# ProProject_audio_project_2024-04-19.net
KiCad netlist of a schematic drawn in EasyEDA Pro
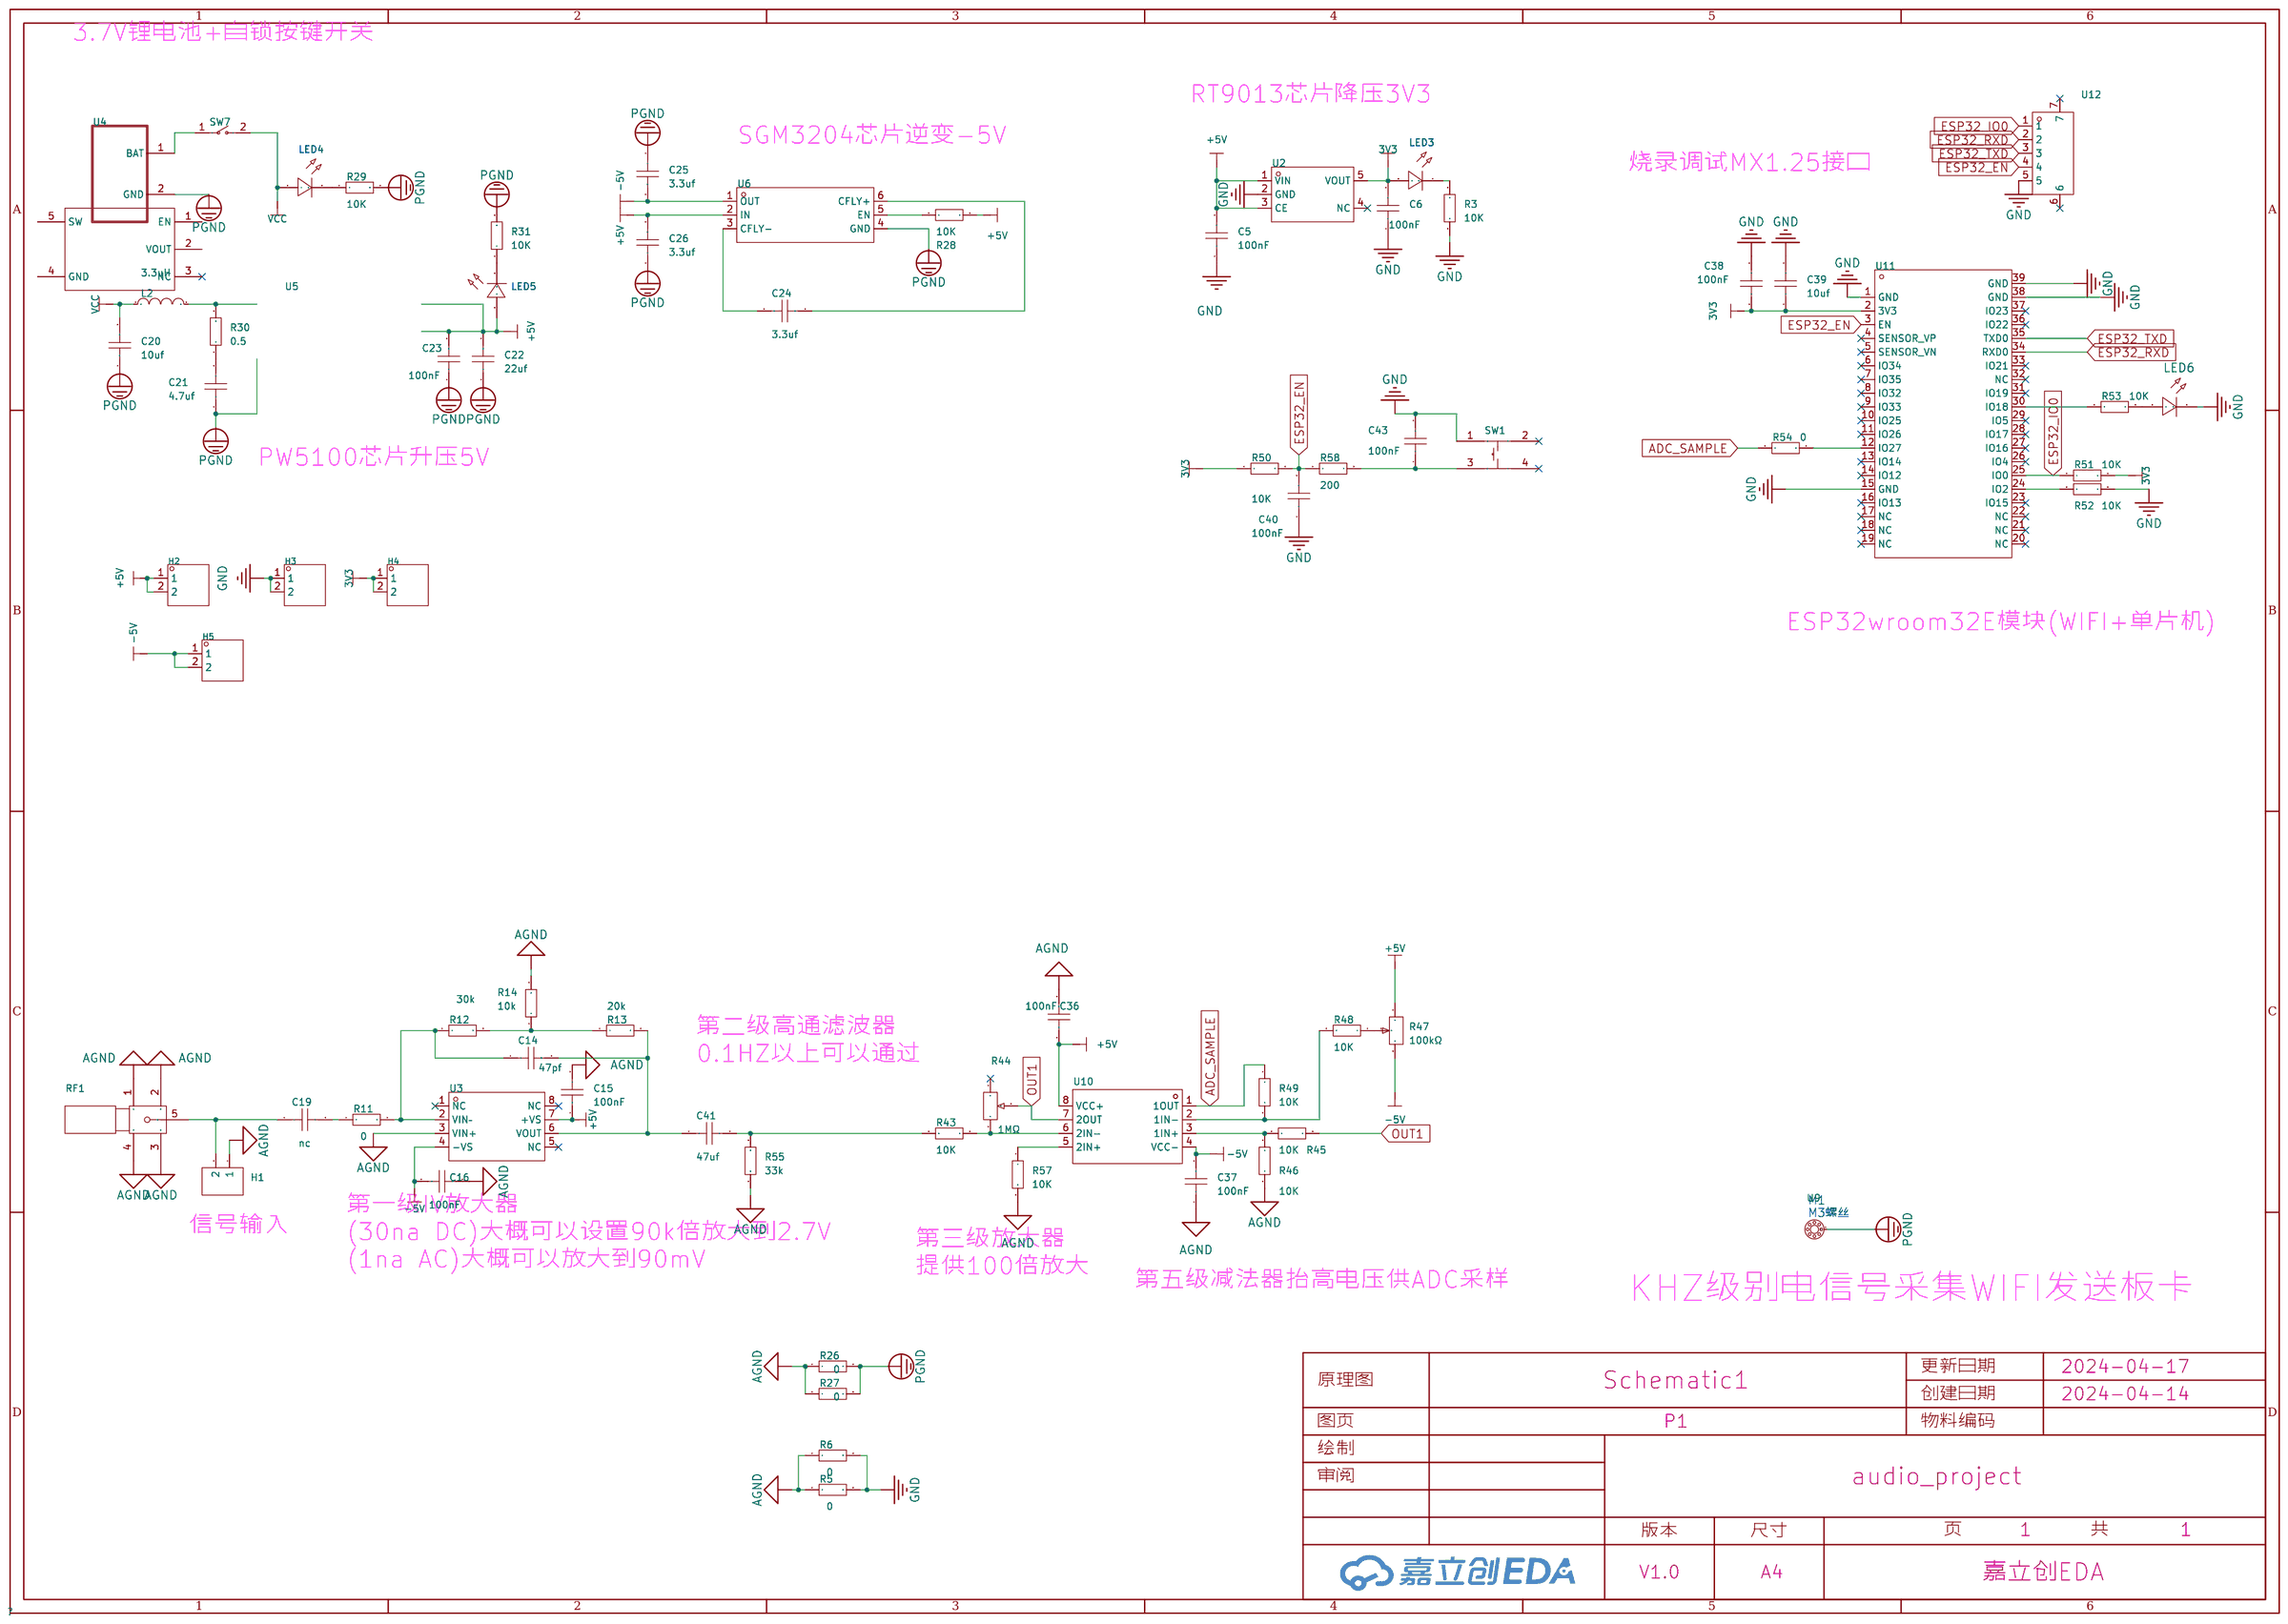
[diagram p0: schematic sheet]

(export (version "E")
  (design (tool "Eeschema 10.0.6"))
  (components
    (comp (ref "C5")
      (value "100nF")
      (footprint "easyedapro:C0805")
      (libsource (lib "easyedapro") (part "CapAcitance"))
    )
    (comp (ref "C6")
      (value "100nF")
      (footprint "easyedapro:C0805")
      (libsource (lib "easyedapro") (part "CapAcitance"))
    )
    (comp (ref "C14")
      (value "47pf")
      (footprint "easyedapro:C0805")
      (libsource (lib "easyedapro") (part "CapAcitance"))
    )
    (comp (ref "C15")
      (value "100nF")
      (footprint "easyedapro:C0805")
      (libsource (lib "easyedapro") (part "CapAcitance"))
    )
    (comp (ref "C16")
      (value "100nF")
      (footprint "easyedapro:C0805")
      (libsource (lib "easyedapro") (part "CapAcitance"))
    )
    (comp (ref "C19")
      (value "nc")
      (footprint "easyedapro:C0805")
      (libsource (lib "easyedapro") (part "CapAcitance"))
    )
    (comp (ref "C20")
      (value "10uf")
      (footprint "easyedapro:C0805")
      (libsource (lib "easyedapro") (part "CapAcitance"))
    )
    (comp (ref "C21")
      (value "4.7uf")
      (footprint "easyedapro:C0805")
      (libsource (lib "easyedapro") (part "CapAcitance"))
    )
    (comp (ref "C22")
      (value "22uf")
      (footprint "easyedapro:C0805")
      (libsource (lib "easyedapro") (part "CapAcitance"))
    )
    (comp (ref "C23")
      (value "100nF")
      (footprint "easyedapro:C0805")
      (libsource (lib "easyedapro") (part "CapAcitance"))
    )
    (comp (ref "C24")
      (value "3.3uf")
      (footprint "easyedapro:C0805")
      (libsource (lib "easyedapro") (part "CapAcitance"))
    )
    (comp (ref "C25")
      (value "3.3uf")
      (footprint "easyedapro:C0805")
      (libsource (lib "easyedapro") (part "CapAcitance"))
    )
    (comp (ref "C26")
      (value "3.3uf")
      (footprint "easyedapro:C0805")
      (libsource (lib "easyedapro") (part "CapAcitance"))
    )
    (comp (ref "C36")
      (value "100nF")
      (footprint "easyedapro:C0805")
      (libsource (lib "easyedapro") (part "CapAcitance"))
    )
    (comp (ref "C37")
      (value "100nF")
      (footprint "easyedapro:C0805")
      (libsource (lib "easyedapro") (part "CapAcitance"))
    )
    (comp (ref "C38")
      (value "100nF")
      (footprint "easyedapro:C0805")
      (libsource (lib "easyedapro") (part "CapAcitance"))
    )
    (comp (ref "C39")
      (value "10uf")
      (footprint "easyedapro:C0805")
      (libsource (lib "easyedapro") (part "CapAcitance"))
    )
    (comp (ref "C40")
      (value "100nF")
      (footprint "easyedapro:C0805")
      (libsource (lib "easyedapro") (part "CapAcitance"))
    )
    (comp (ref "C41")
      (value "47uf")
      (footprint "easyedapro:C0805")
      (libsource (lib "easyedapro") (part "CapAcitance"))
    )
    (comp (ref "C43")
      (value "100nF")
      (footprint "easyedapro:C0805")
      (libsource (lib "easyedapro") (part "CapAcitance"))
    )
    (comp (ref "H1")
      (value "~")
      (footprint "easyedapro:HDR-TH_2P-P2.54-V-F")
      (libsource (lib "easyedapro") (part "Header-Female-2.54_1x2"))
    )
    (comp (ref "H2")
      (value "~")
      (footprint "easyedapro:HDR-TH_2P-P2.54-V-M-1")
      (libsource (lib "easyedapro") (part "210S-1*2P L=11.6MMGold-plated black"))
    )
    (comp (ref "H3")
      (value "~")
      (footprint "easyedapro:HDR-TH_2P-P2.54-V-M-1")
      (libsource (lib "easyedapro") (part "210S-1*2P L=11.6MMGold-plated black"))
    )
    (comp (ref "H4")
      (value "~")
      (footprint "easyedapro:HDR-TH_2P-P2.54-V-M-1")
      (libsource (lib "easyedapro") (part "210S-1*2P L=11.6MMGold-plated black"))
    )
    (comp (ref "H5")
      (value "~")
      (footprint "easyedapro:HDR-TH_2P-P2.54-V-M-1")
      (libsource (lib "easyedapro") (part "210S-1*2P L=11.6MMGold-plated black"))
    )
    (comp (ref "L2")
      (value "3.3uH")
      (footprint "easyedapro:IND-SMD_L4.0-W4.0_FNR40XXS")
      (description "电感值:3.3uH;精度:±20%;额定电流:2.6A;饱和电流(Isat):3.6A;")
      (fields (field (name "Manufacturer Part") "FNR4030S3R3MT") (field (name "Manufacturer") "cjiang(长江微电)"))
      (libsource (lib "easyedapro") (part "FNR4030S3R3MT"))
    )
    (comp (ref "LED3")
      (value "~")
      (footprint "easyedapro:LED_0805")
      (libsource (lib "easyedapro") (part "LED_G"))
    )
    (comp (ref "LED4")
      (value "~")
      (footprint "easyedapro:LED_0805")
      (libsource (lib "easyedapro") (part "LED_G"))
    )
    (comp (ref "LED5")
      (value "~")
      (footprint "easyedapro:LED_0805")
      (libsource (lib "easyedapro") (part "LED_G"))
    )
    (comp (ref "LED6")
      (value "~")
      (footprint "easyedapro:LED_0805")
      (libsource (lib "easyedapro") (part "LED_R"))
    )
    (comp (ref "R3") (value "10K") (footprint "easyedapro:R0603") (libsource (lib "easyedapro") (part "电阻")))
    (comp (ref "R5") (value "0") (footprint "easyedapro:R0603") (libsource (lib "easyedapro") (part "电阻")))
    (comp (ref "R6") (value "0") (footprint "easyedapro:R0603") (libsource (lib "easyedapro") (part "电阻")))
    (comp (ref "R11") (value "0") (footprint "easyedapro:R0603") (libsource (lib "easyedapro") (part "电阻")))
    (comp (ref "R12") (value "30k") (footprint "easyedapro:R0603") (libsource (lib "easyedapro") (part "电阻")))
    (comp (ref "R13") (value "20k") (footprint "easyedapro:R0603") (libsource (lib "easyedapro") (part "电阻")))
    (comp (ref "R14") (value "10k") (footprint "easyedapro:R0603") (libsource (lib "easyedapro") (part "电阻")))
    (comp (ref "R26") (value "0") (footprint "easyedapro:R0603") (libsource (lib "easyedapro") (part "电阻")))
    (comp (ref "R27") (value "0") (footprint "easyedapro:R0603") (libsource (lib "easyedapro") (part "电阻")))
    (comp (ref "R28") (value "10K") (footprint "easyedapro:R0603") (libsource (lib "easyedapro") (part "电阻")))
    (comp (ref "R29") (value "10K") (footprint "easyedapro:R0603") (libsource (lib "easyedapro") (part "电阻")))
    (comp (ref "R30") (value "0.5") (footprint "easyedapro:R0603") (libsource (lib "easyedapro") (part "电阻")))
    (comp (ref "R31") (value "10K") (footprint "easyedapro:R0603") (libsource (lib "easyedapro") (part "电阻")))
    (comp (ref "R43") (value "10K") (footprint "easyedapro:R0603") (libsource (lib "easyedapro") (part "电阻")))
    (comp (ref "R44")
      (value "1MΩ")
      (footprint "easyedapro:RES-ADJ-TH_3P-L7.1-W6.9-P2.50-L_3362P")
      (description "阻值:1MΩ;精度:±10%;")
      (fields (field (name "Manufacturer Part") "3362P-1-105") (field (name "Manufacturer") "BOCHEN(博晨)"))
      (libsource (lib "easyedapro") (part "3362P-1-105_C118945"))
    )
    (comp (ref "R45") (value "10K") (footprint "easyedapro:R0603") (libsource (lib "easyedapro") (part "电阻")))
    (comp (ref "R46") (value "10K") (footprint "easyedapro:R0603") (libsource (lib "easyedapro") (part "电阻")))
    (comp (ref "R47")
      (value "100kΩ")
      (footprint "easyedapro:RES-ADJ-TH_3296W")
      (description "阻值:100kΩ;精度:±10%;")
      (fields (field (name "Manufacturer Part") "3296W-1-104LF") (field (name "Manufacturer") "BOURNS"))
      (libsource (lib "easyedapro") (part "3296W-1-104LF"))
    )
    (comp (ref "R48") (value "10K") (footprint "easyedapro:R0603") (libsource (lib "easyedapro") (part "电阻")))
    (comp (ref "R49") (value "10K") (footprint "easyedapro:R0603") (libsource (lib "easyedapro") (part "电阻")))
    (comp (ref "R50") (value "10K") (footprint "easyedapro:R0603") (libsource (lib "easyedapro") (part "电阻")))
    (comp (ref "R51") (value "10K") (footprint "easyedapro:R0603") (libsource (lib "easyedapro") (part "电阻")))
    (comp (ref "R52") (value "10K") (footprint "easyedapro:R0603") (libsource (lib "easyedapro") (part "电阻")))
    (comp (ref "R53") (value "10K") (footprint "easyedapro:R0603") (libsource (lib "easyedapro") (part "电阻")))
    (comp (ref "R54") (value "0") (footprint "easyedapro:R0603") (libsource (lib "easyedapro") (part "电阻")))
    (comp (ref "R55") (value "33k") (footprint "easyedapro:R0603") (libsource (lib "easyedapro") (part "电阻")))
    (comp (ref "R57") (value "10K") (footprint "easyedapro:R0603") (libsource (lib "easyedapro") (part "电阻")))
    (comp (ref "R58") (value "200") (footprint "easyedapro:R0603") (libsource (lib "easyedapro") (part "电阻")))
    (comp (ref "RF1")
      (value "BWSMA-KWE-Z001")
      (footprint "easyedapro:SMA-TH_BWSMA-KWE-Z001")
      (fields (field (name "Manufacturer") "BAT WIRELESS(蝙蝠无线)"))
      (libsource (lib "easyedapro") (part "BWSMA-KWE-Z001"))
    )
    (comp (ref "SW1")
      (value "K2-1808SN-A3SW-01")
      (footprint "easyedapro:SW-SMD_4P-L4.2-W3.3-P2.15-LS5.1")
      (fields (field (name "Manufacturer") "韩国韩荣"))
      (libsource (lib "easyedapro") (part "K2-1808SN-A3SW-01"))
    )
    (comp (ref "SW7")
      (value "KCD11-2P-R")
      (footprint "easyedapro:SW-TH_2P-L15.0-W10.5-P5.00_KCD11-2P-R")
      (description "带灯:无;引脚样式:焊片;额定电流:3A;额定电压(AC):250V;额定电压(DC):-;电路结构:单刀单掷;机械寿命:1万次;")
      (fields (field (name "Manufacturer") "SHOU HAN(首韩)"))
      (libsource (lib "easyedapro") (part "KCD11-2P-R"))
    )
    (comp (ref "U2")
      (value "RT9013-33GB-MS")
      (footprint "easyedapro:SOT-23-5_L2.9-W1.6-P0.95-LS2.8-BR")
      (description "输出类型:固定;最大输入电压:5.5V;输出电压:3.3V;输出电流:500mA;电源纹波抑制比(PSRR):75dB@(1kHz);输出极性:正极;")
      (fields (field (name "Manufacturer") "MSKSEMI(美森科)"))
      (libsource (lib "easyedapro") (part "RT9013-33GB-MS"))
    )
    (comp (ref "U3")
      (value "OPA657U")
      (footprint "easyedapro:SOIC-8_L4.9-W3.9-P1.27-LS6.0-TL")
      (description "1.6GHz、低噪声、FET 输入运算放大器 8-SOIC -40 to 85")
      (fields (field (name "Manufacturer") "TI(德州仪器)"))
      (libsource (lib "easyedapro") (part "OPA657U"))
    )
    (comp (ref "U4") (value "~") (footprint "easyedapro:两个焊盘") (libsource (lib "easyedapro") (part "两个焊盘")))
    (comp (ref "U5")
      (value "3c0bada92d29401ea73ee46ec49cffd6")
      (footprint "easyedapro:SOT-23-5_L2.9-W1.6-P0.95-LS2.8-TL")
      (description "锂电池DC-DC高效同步升压变换器")
      (libsource (lib "easyedapro") (part "PW5100"))
    )
    (comp (ref "U6")
      (value "SGM3204YN6G/TR")
      (footprint "easyedapro:SOT-23-6_L2.9-W1.6-P0.95-LS2.8-BR")
      (description "功能类型:电荷泵;输入电压:1.4V~5.5V;输出电压:-5.5V~-1.4V;输出电流(最大值):200mA;")
      (fields (field (name "Manufacturer") "SGMICRO(圣邦微)"))
      (libsource (lib "easyedapro") (part "SGM3204YN6G/TR"))
    )
    (comp (ref "U9") (value "~") (libsource (lib "easyedapro") (part "M3焊盘")))
    (comp (ref "U10")
      (value "LF353DR")
      (footprint "easyedapro:SOIC-8_L5.0-W4.0-P1.27-LS6.0-BL")
      (description "运放类型:J-FET;放大器组数:2;增益带宽积（GBP）:3MHz;压摆率（SR）:13 V/us;电源电压:±3.5V ~ 18V;各通道供电电流:3.6mA;")
      (fields (field (name "Manufacturer") "TI(德州仪器)"))
      (libsource (lib "easyedapro") (part "LF353DRG4"))
    )
    (comp (ref "U11")
      (value "ESP32-WROOM-32E")
      (footprint "easyedapro:WIFI-SMD_ESP32-WROOM-32E-A")
      (fields (field (name "Manufacturer") "ESPRESSIF(乐鑫)"))
      (libsource (lib "easyedapro") (part "ESP32-WROOM-32E-N4"))
    )
    (comp (ref "U12")
      (value "ZX-MX1.25-5PLT")
      (footprint "easyedapro:CONN-SMD_5P-P1.25_MEGASTAR_ZX-MX1.25-5PLT")
      (fields (field (name "Manufacturer") "Megastar(兆星)"))
      (libsource (lib "easyedapro") (part "ZX-MX1.25-5PLT"))
    )
  )
  (nets
    (net (code "1") (name "+5V") (class "Default")
      (node (ref "C15") (pin "1") (pinfunction "1_1") (pintype "input"))
      (node (ref "C22") (pin "2") (pinfunction "2_2") (pintype "input"))
      (node (ref "C23") (pin "2") (pinfunction "2_2") (pintype "input"))
      (node (ref "C26") (pin "2") (pinfunction "2_2") (pintype "input"))
      (node (ref "C36") (pin "1") (pinfunction "1_1") (pintype "input"))
      (node (ref "C5") (pin "2") (pinfunction "2_2") (pintype "input"))
      (node (ref "H2") (pin "1") (pinfunction "1_1") (pintype "input"))
      (node (ref "H2") (pin "2") (pinfunction "2_2") (pintype "input"))
      (node (ref "LED5") (pin "2") (pinfunction "A_2") (pintype "input"))
      (node (ref "R28") (pin "2") (pinfunction "2_2") (pintype "input"))
      (node (ref "R47") (pin "1") (pinfunction "1_1") (pintype "input"))
      (node (ref "U10") (pin "8") (pinfunction "VCC+_8") (pintype "input"))
      (node (ref "U2") (pin "1") (pinfunction "VIN_1") (pintype "unspecified"))
      (node (ref "U2") (pin "3") (pinfunction "CE_3") (pintype "unspecified"))
      (node (ref "U3") (pin "7") (pinfunction "+VS_7") (pintype "input"))
      (node (ref "U6") (pin "2") (pinfunction "IN_2") (pintype "unspecified"))
    )
    (net (code "2") (name "-5V") (class "Default")
      (node (ref "C16") (pin "2") (pinfunction "2_2") (pintype "input"))
      (node (ref "C25") (pin "2") (pinfunction "2_2") (pintype "input"))
      (node (ref "C37") (pin "2") (pinfunction "2_2") (pintype "input"))
      (node (ref "H5") (pin "1") (pinfunction "1_1") (pintype "input"))
      (node (ref "H5") (pin "2") (pinfunction "2_2") (pintype "input"))
      (node (ref "R47") (pin "3") (pinfunction "3_3") (pintype "input"))
      (node (ref "U10") (pin "4") (pinfunction "VCC-_4") (pintype "input"))
      (node (ref "U3") (pin "4") (pinfunction "-VS_4") (pintype "input"))
      (node (ref "U6") (pin "1") (pinfunction "OUT_1") (pintype "unspecified"))
    )
    (net (code "3") (name "3V3") (class "Default")
      (node (ref "C38") (pin "2") (pinfunction "2_2") (pintype "input"))
      (node (ref "C39") (pin "1") (pinfunction "1_1") (pintype "input"))
      (node (ref "C6") (pin "2") (pinfunction "2_2") (pintype "input"))
      (node (ref "H4") (pin "1") (pinfunction "1_1") (pintype "input"))
      (node (ref "H4") (pin "2") (pinfunction "2_2") (pintype "input"))
      (node (ref "LED3") (pin "2") (pinfunction "A_2") (pintype "input"))
      (node (ref "R50") (pin "1") (pinfunction "1_1") (pintype "input"))
      (node (ref "R51") (pin "2") (pinfunction "2_2") (pintype "input"))
      (node (ref "U11") (pin "2") (pinfunction "3V3_2") (pintype "unspecified"))
      (node (ref "U2") (pin "5") (pinfunction "VOUT_5") (pintype "unspecified"))
    )
    (net (code "4") (name "ADC_SAMPLE") (class "Default")
      (node (ref "R49") (pin "1") (pinfunction "1_1") (pintype "input"))
      (node (ref "R54") (pin "1") (pinfunction "1_1") (pintype "input"))
      (node (ref "U10") (pin "1") (pinfunction "1OUT_1") (pintype "input"))
    )
    (net (code "5") (name "AGND") (class "Default")
      (node (ref "C15") (pin "2") (pinfunction "2_2") (pintype "input"))
      (node (ref "C16") (pin "1") (pinfunction "1_1") (pintype "input"))
      (node (ref "C36") (pin "2") (pinfunction "2_2") (pintype "input"))
      (node (ref "C37") (pin "1") (pinfunction "1_1") (pintype "input"))
      (node (ref "H1") (pin "1") (pinfunction "1_1") (pintype "input"))
      (node (ref "R14") (pin "2") (pinfunction "2_2") (pintype "input"))
      (node (ref "R26") (pin "1") (pinfunction "1_1") (pintype "input"))
      (node (ref "R27") (pin "1") (pinfunction "1_1") (pintype "input"))
      (node (ref "R46") (pin "1") (pinfunction "1_1") (pintype "input"))
      (node (ref "R5") (pin "1") (pinfunction "1_1") (pintype "input"))
      (node (ref "R55") (pin "1") (pinfunction "1_1") (pintype "input"))
      (node (ref "R57") (pin "2") (pinfunction "2_2") (pintype "input"))
      (node (ref "R6") (pin "1") (pinfunction "1_1") (pintype "input"))
      (node (ref "RF1") (pin "1") (pinfunction "1_1") (pintype "unspecified"))
      (node (ref "RF1") (pin "2") (pinfunction "2_2") (pintype "unspecified"))
      (node (ref "RF1") (pin "3") (pinfunction "3_3") (pintype "unspecified"))
      (node (ref "RF1") (pin "4") (pinfunction "4_4") (pintype "unspecified"))
      (node (ref "U3") (pin "3") (pinfunction "VIN+_3") (pintype "input"))
    )
    (net (code "6") (name "ESP32_EN") (class "Default")
      (node (ref "C40") (pin "2") (pinfunction "2_2") (pintype "input"))
      (node (ref "R50") (pin "2") (pinfunction "2_2") (pintype "input"))
      (node (ref "R58") (pin "1") (pinfunction "1_1") (pintype "input"))
      (node (ref "U11") (pin "3") (pinfunction "EN_3") (pintype "unspecified"))
      (node (ref "U12") (pin "4") (pinfunction "4_4") (pintype "unspecified"))
    )
    (net (code "7") (name "ESP32_IO0") (class "Default")
      (node (ref "R51") (pin "1") (pinfunction "1_1") (pintype "input"))
      (node (ref "U11") (pin "25") (pinfunction "IO0_25") (pintype "unspecified"))
      (node (ref "U12") (pin "1") (pinfunction "1_1") (pintype "unspecified"))
    )
    (net (code "8") (name "ESP32_RXD") (class "Default")
      (node (ref "U11") (pin "34") (pinfunction "RXD0_34") (pintype "unspecified"))
      (node (ref "U12") (pin "2") (pinfunction "2_2") (pintype "unspecified"))
    )
    (net (code "9") (name "ESP32_TXD") (class "Default")
      (node (ref "U11") (pin "35") (pinfunction "TXD0_35") (pintype "unspecified"))
      (node (ref "U12") (pin "3") (pinfunction "3_3") (pintype "unspecified"))
    )
    (net (code "10") (name "GND") (class "Default")
      (node (ref "C38") (pin "1") (pinfunction "1_1") (pintype "input"))
      (node (ref "C39") (pin "2") (pinfunction "2_2") (pintype "input"))
      (node (ref "C40") (pin "1") (pinfunction "1_1") (pintype "input"))
      (node (ref "C43") (pin "2") (pinfunction "2_2") (pintype "input"))
      (node (ref "C5") (pin "1") (pinfunction "1_1") (pintype "input"))
      (node (ref "C6") (pin "1") (pinfunction "1_1") (pintype "input"))
      (node (ref "H3") (pin "1") (pinfunction "1_1") (pintype "input"))
      (node (ref "H3") (pin "2") (pinfunction "2_2") (pintype "input"))
      (node (ref "LED6") (pin "1") (pinfunction "C_1") (pintype "input"))
      (node (ref "R3") (pin "2") (pinfunction "2_2") (pintype "input"))
      (node (ref "R5") (pin "2") (pinfunction "2_2") (pintype "input"))
      (node (ref "R52") (pin "2") (pinfunction "2_2") (pintype "input"))
      (node (ref "R6") (pin "2") (pinfunction "2_2") (pintype "input"))
      (node (ref "SW1") (pin "1") (pinfunction "1_1") (pintype "input"))
      (node (ref "U11") (pin "1") (pinfunction "GND_1") (pintype "unspecified"))
      (node (ref "U11") (pin "15") (pinfunction "GND_15") (pintype "unspecified"))
      (node (ref "U11") (pin "38") (pinfunction "GND_38") (pintype "unspecified"))
      (node (ref "U11") (pin "39") (pinfunction "GND_39") (pintype "unspecified"))
      (node (ref "U12") (pin "5") (pinfunction "5_5") (pintype "unspecified"))
      (node (ref "U2") (pin "2") (pinfunction "GND_2") (pintype "unspecified"))
    )
    (net (code "11") (name "Net-(C19-Pad1)") (class "Default")
      (node (ref "C19") (pin "1") (pinfunction "1_1") (pintype "input"))
      (node (ref "H1") (pin "2") (pinfunction "2_2") (pintype "input"))
      (node (ref "RF1") (pin "5") (pinfunction "5_5") (pintype "unspecified"))
    )
    (net (code "12") (name "Net-(C19-Pad2)") (class "Default")
      (node (ref "C19") (pin "2") (pinfunction "2_2") (pintype "input"))
      (node (ref "R11") (pin "1") (pinfunction "1_1") (pintype "input"))
    )
    (net (code "13") (name "Net-(C21-Pad2)") (class "Default")
      (node (ref "C21") (pin "2") (pinfunction "2_2") (pintype "input"))
      (node (ref "R30") (pin "1") (pinfunction "1_1") (pintype "input"))
    )
    (net (code "14") (name "Net-(C41-Pad2)") (class "Default")
      (node (ref "C41") (pin "2") (pinfunction "2_2") (pintype "input"))
      (node (ref "R43") (pin "2") (pinfunction "2_2") (pintype "input"))
      (node (ref "R55") (pin "2") (pinfunction "2_2") (pintype "input"))
    )
    (net (code "15") (name "Net-(C43-Pad1)") (class "Default")
      (node (ref "C43") (pin "1") (pinfunction "1_1") (pintype "input"))
      (node (ref "R58") (pin "2") (pinfunction "2_2") (pintype "input"))
      (node (ref "SW1") (pin "3") (pinfunction "3_3") (pintype "input"))
    )
    (net (code "16") (name "Net-(L2-Pad2)") (class "Default")
      (node (ref "L2") (pin "2") (pinfunction "2_2") (pintype "unspecified"))
      (node (ref "R30") (pin "2") (pinfunction "2_2") (pintype "input"))
    )
    (net (code "17") (name "Net-(LED3-C)") (class "Default")
      (node (ref "LED3") (pin "1") (pinfunction "C_1") (pintype "input"))
      (node (ref "R3") (pin "1") (pinfunction "1_1") (pintype "input"))
    )
    (net (code "18") (name "Net-(LED4-C)") (class "Default")
      (node (ref "LED4") (pin "1") (pinfunction "C_1") (pintype "input"))
      (node (ref "R29") (pin "1") (pinfunction "1_1") (pintype "input"))
    )
    (net (code "19") (name "Net-(LED5-C)") (class "Default")
      (node (ref "LED5") (pin "1") (pinfunction "C_1") (pintype "input"))
      (node (ref "R31") (pin "1") (pinfunction "1_1") (pintype "input"))
    )
    (net (code "20") (name "Net-(LED6-A)") (class "Default")
      (node (ref "LED6") (pin "2") (pinfunction "A_2") (pintype "input"))
      (node (ref "R53") (pin "2") (pinfunction "2_2") (pintype "input"))
    )
    (net (code "21") (name "Net-(R12-Pad2)") (class "Default")
      (node (ref "R12") (pin "2") (pinfunction "2_2") (pintype "input"))
      (node (ref "R13") (pin "1") (pinfunction "1_1") (pintype "input"))
      (node (ref "R14") (pin "1") (pinfunction "1_1") (pintype "input"))
    )
    (net (code "22") (name "Net-(R47-Pad2)") (class "Default")
      (node (ref "R47") (pin "2") (pinfunction "2_2") (pintype "input"))
      (node (ref "R48") (pin "1") (pinfunction "1_1") (pintype "input"))
    )
    (net (code "23") (name "Net-(U3-VIN–)") (class "Default")
      (node (ref "C14") (pin "1") (pinfunction "1_1") (pintype "input"))
      (node (ref "R11") (pin "2") (pinfunction "2_2") (pintype "input"))
      (node (ref "R12") (pin "1") (pinfunction "1_1") (pintype "input"))
      (node (ref "U3") (pin "2") (pinfunction "VIN–_2") (pintype "input"))
    )
    (net (code "24") (name "Net-(U3-VOUT)") (class "Default")
      (node (ref "C14") (pin "2") (pinfunction "2_2") (pintype "input"))
      (node (ref "C41") (pin "1") (pinfunction "1_1") (pintype "input"))
      (node (ref "R13") (pin "2") (pinfunction "2_2") (pintype "input"))
      (node (ref "U3") (pin "6") (pinfunction "VOUT_6") (pintype "input"))
    )
    (net (code "25") (name "Net-(U4-BAT)") (class "Default")
      (node (ref "SW7") (pin "1") (pinfunction "1_1") (pintype "unspecified"))
      (node (ref "U4") (pin "1") (pinfunction "BAT_1") (pintype "input"))
    )
    (net (code "26") (name "Net-(U6-CFLY+)") (class "Default")
      (node (ref "C24") (pin "1") (pinfunction "1_1") (pintype "input"))
      (node (ref "U6") (pin "6") (pinfunction "CFLY+_6") (pintype "unspecified"))
    )
    (net (code "27") (name "Net-(U6-CFLY-)") (class "Default")
      (node (ref "C24") (pin "2") (pinfunction "2_2") (pintype "input"))
      (node (ref "U6") (pin "3") (pinfunction "CFLY-_3") (pintype "unspecified"))
    )
    (net (code "28") (name "Net-(U6-EN)") (class "Default")
      (node (ref "R28") (pin "1") (pinfunction "1_1") (pintype "input"))
      (node (ref "U6") (pin "5") (pinfunction "EN_5") (pintype "unspecified"))
    )
    (net (code "29") (name "Net-(U10-1IN+)") (class "Default")
      (node (ref "R45") (pin "1") (pinfunction "1_1") (pintype "input"))
      (node (ref "R46") (pin "2") (pinfunction "2_2") (pintype "input"))
      (node (ref "U10") (pin "3") (pinfunction "1IN+_3") (pintype "input"))
    )
    (net (code "30") (name "Net-(U10-1IN-)") (class "Default")
      (node (ref "R48") (pin "2") (pinfunction "2_2") (pintype "input"))
      (node (ref "R49") (pin "2") (pinfunction "2_2") (pintype "input"))
      (node (ref "U10") (pin "2") (pinfunction "1IN-_2") (pintype "input"))
    )
    (net (code "31") (name "Net-(U10-2IN+)") (class "Default")
      (node (ref "R57") (pin "1") (pinfunction "1_1") (pintype "input"))
      (node (ref "U10") (pin "5") (pinfunction "2IN+_5") (pintype "input"))
    )
    (net (code "32") (name "Net-(U10-2IN-)") (class "Default")
      (node (ref "R43") (pin "1") (pinfunction "1_1") (pintype "input"))
      (node (ref "R44") (pin "3") (pinfunction "3_3") (pintype "input"))
      (node (ref "U10") (pin "6") (pinfunction "2IN-_6") (pintype "input"))
    )
    (net (code "33") (name "Net-(U11-IO2)") (class "Default")
      (node (ref "R52") (pin "1") (pinfunction "1_1") (pintype "input"))
      (node (ref "U11") (pin "24") (pinfunction "IO2_24") (pintype "unspecified"))
    )
    (net (code "34") (name "Net-(U11-IO18)") (class "Default")
      (node (ref "R53") (pin "1") (pinfunction "1_1") (pintype "input"))
      (node (ref "U11") (pin "30") (pinfunction "IO18_30") (pintype "unspecified"))
    )
    (net (code "35") (name "Net-(U11-IO27)") (class "Default")
      (node (ref "R54") (pin "2") (pinfunction "2_2") (pintype "input"))
      (node (ref "U11") (pin "12") (pinfunction "IO27_12") (pintype "unspecified"))
    )
    (net (code "36") (name "OUT1") (class "Default")
      (node (ref "R44") (pin "2") (pinfunction "2_2") (pintype "input"))
      (node (ref "R45") (pin "2") (pinfunction "2_2") (pintype "input"))
      (node (ref "U10") (pin "7") (pinfunction "2OUT_7") (pintype "input"))
    )
    (net (code "37") (name "PGND") (class "Default")
      (node (ref "C20") (pin "1") (pinfunction "1_1") (pintype "input"))
      (node (ref "C21") (pin "1") (pinfunction "1_1") (pintype "input"))
      (node (ref "C22") (pin "1") (pinfunction "1_1") (pintype "input"))
      (node (ref "C23") (pin "1") (pinfunction "1_1") (pintype "input"))
      (node (ref "C25") (pin "1") (pinfunction "1_1") (pintype "input"))
      (node (ref "C26") (pin "1") (pinfunction "1_1") (pintype "input"))
      (node (ref "R26") (pin "2") (pinfunction "2_2") (pintype "input"))
      (node (ref "R27") (pin "2") (pinfunction "2_2") (pintype "input"))
      (node (ref "R29") (pin "2") (pinfunction "2_2") (pintype "input"))
      (node (ref "R31") (pin "2") (pinfunction "2_2") (pintype "input"))
      (node (ref "U4") (pin "2") (pinfunction "GND_2") (pintype "input"))
      (node (ref "U6") (pin "4") (pinfunction "GND_4") (pintype "unspecified"))
      (node (ref "U9") (pin "1") (pinfunction "1_1") (pintype "input"))
    )
    (net (code "38") (name "VCC") (class "Default")
      (node (ref "C20") (pin "2") (pinfunction "2_2") (pintype "input"))
      (node (ref "L2") (pin "1") (pinfunction "1_1") (pintype "unspecified"))
      (node (ref "LED4") (pin "2") (pinfunction "A_2") (pintype "input"))
      (node (ref "SW7") (pin "2") (pinfunction "2_2") (pintype "unspecified"))
    )
    (net (code "39") (name "unconnected-(R44-Pad1)") (class "Default")
      (node (ref "R44") (pin "1") (pinfunction "1_1") (pintype "input+no_connect"))
    )
    (net (code "40") (name "unconnected-(SW1-Pad2)") (class "Default")
      (node (ref "SW1") (pin "2") (pinfunction "2_2") (pintype "input+no_connect"))
    )
    (net (code "41") (name "unconnected-(SW1-Pad4)") (class "Default")
      (node (ref "SW1") (pin "4") (pinfunction "4_4") (pintype "input+no_connect"))
    )
    (net (code "42") (name "unconnected-(U2-NC-Pad4)") (class "Default")
      (node (ref "U2") (pin "4") (pinfunction "NC_4") (pintype "unspecified+no_connect"))
    )
    (net (code "43") (name "unconnected-(U3-NC-Pad1)") (class "Default")
      (node (ref "U3") (pin "1") (pinfunction "NC_1") (pintype "input+no_connect"))
    )
    (net (code "44") (name "unconnected-(U3-NC-Pad5)") (class "Default")
      (node (ref "U3") (pin "5") (pinfunction "NC_5") (pintype "input+no_connect"))
    )
    (net (code "45") (name "unconnected-(U3-NC-Pad8)") (class "Default")
      (node (ref "U3") (pin "8") (pinfunction "NC_8") (pintype "input+no_connect"))
    )
    (net (code "46") (name "unconnected-(U5-EN-Pad1)") (class "Default")
      (node (ref "U5") (pin "1") (pinfunction "EN_1") (pintype "input"))
    )
    (net (code "47") (name "unconnected-(U5-GND-Pad4)") (class "Default")
      (node (ref "U5") (pin "4") (pinfunction "GND_4") (pintype "input"))
    )
    (net (code "48") (name "unconnected-(U5-NC-Pad3)") (class "Default")
      (node (ref "U5") (pin "3") (pinfunction "NC_3") (pintype "input+no_connect"))
    )
    (net (code "49") (name "unconnected-(U5-SW-Pad5)") (class "Default")
      (node (ref "U5") (pin "5") (pinfunction "SW_5") (pintype "input"))
    )
    (net (code "50") (name "unconnected-(U5-VOUT-Pad2)") (class "Default")
      (node (ref "U5") (pin "2") (pinfunction "VOUT_2") (pintype "input"))
    )
    (net (code "51") (name "unconnected-(U11-IO4-Pad26)") (class "Default")
      (node (ref "U11") (pin "26") (pinfunction "IO4_26") (pintype "unspecified+no_connect"))
    )
    (net (code "52") (name "unconnected-(U11-IO5-Pad29)") (class "Default")
      (node (ref "U11") (pin "29") (pinfunction "IO5_29") (pintype "unspecified+no_connect"))
    )
    (net (code "53") (name "unconnected-(U11-IO12-Pad14)") (class "Default")
      (node (ref "U11") (pin "14") (pinfunction "IO12_14") (pintype "unspecified+no_connect"))
    )
    (net (code "54") (name "unconnected-(U11-IO13-Pad16)") (class "Default")
      (node (ref "U11") (pin "16") (pinfunction "IO13_16") (pintype "unspecified+no_connect"))
    )
    (net (code "55") (name "unconnected-(U11-IO14-Pad13)") (class "Default")
      (node (ref "U11") (pin "13") (pinfunction "IO14_13") (pintype "unspecified+no_connect"))
    )
    (net (code "56") (name "unconnected-(U11-IO15-Pad23)") (class "Default")
      (node (ref "U11") (pin "23") (pinfunction "IO15_23") (pintype "unspecified+no_connect"))
    )
    (net (code "57") (name "unconnected-(U11-IO16-Pad27)") (class "Default")
      (node (ref "U11") (pin "27") (pinfunction "IO16_27") (pintype "unspecified+no_connect"))
    )
    (net (code "58") (name "unconnected-(U11-IO17-Pad28)") (class "Default")
      (node (ref "U11") (pin "28") (pinfunction "IO17_28") (pintype "unspecified+no_connect"))
    )
    (net (code "59") (name "unconnected-(U11-IO19-Pad31)") (class "Default")
      (node (ref "U11") (pin "31") (pinfunction "IO19_31") (pintype "unspecified+no_connect"))
    )
    (net (code "60") (name "unconnected-(U11-IO21-Pad33)") (class "Default")
      (node (ref "U11") (pin "33") (pinfunction "IO21_33") (pintype "unspecified+no_connect"))
    )
    (net (code "61") (name "unconnected-(U11-IO22-Pad36)") (class "Default")
      (node (ref "U11") (pin "36") (pinfunction "IO22_36") (pintype "unspecified+no_connect"))
    )
    (net (code "62") (name "unconnected-(U11-IO23-Pad37)") (class "Default")
      (node (ref "U11") (pin "37") (pinfunction "IO23_37") (pintype "unspecified+no_connect"))
    )
    (net (code "63") (name "unconnected-(U11-IO25-Pad10)") (class "Default")
      (node (ref "U11") (pin "10") (pinfunction "IO25_10") (pintype "unspecified+no_connect"))
    )
    (net (code "64") (name "unconnected-(U11-IO26-Pad11)") (class "Default")
      (node (ref "U11") (pin "11") (pinfunction "IO26_11") (pintype "unspecified+no_connect"))
    )
    (net (code "65") (name "unconnected-(U11-IO32-Pad8)") (class "Default")
      (node (ref "U11") (pin "8") (pinfunction "IO32_8") (pintype "unspecified+no_connect"))
    )
    (net (code "66") (name "unconnected-(U11-IO33-Pad9)") (class "Default")
      (node (ref "U11") (pin "9") (pinfunction "IO33_9") (pintype "unspecified+no_connect"))
    )
    (net (code "67") (name "unconnected-(U11-IO34-Pad6)") (class "Default")
      (node (ref "U11") (pin "6") (pinfunction "IO34_6") (pintype "unspecified+no_connect"))
    )
    (net (code "68") (name "unconnected-(U11-IO35-Pad7)") (class "Default")
      (node (ref "U11") (pin "7") (pinfunction "IO35_7") (pintype "unspecified+no_connect"))
    )
    (net (code "69") (name "unconnected-(U11-NC-Pad17)") (class "Default")
      (node (ref "U11") (pin "17") (pinfunction "NC_17") (pintype "unspecified+no_connect"))
    )
    (net (code "70") (name "unconnected-(U11-NC-Pad18)") (class "Default")
      (node (ref "U11") (pin "18") (pinfunction "NC_18") (pintype "unspecified+no_connect"))
    )
    (net (code "71") (name "unconnected-(U11-NC-Pad19)") (class "Default")
      (node (ref "U11") (pin "19") (pinfunction "NC_19") (pintype "unspecified+no_connect"))
    )
    (net (code "72") (name "unconnected-(U11-NC-Pad20)") (class "Default")
      (node (ref "U11") (pin "20") (pinfunction "NC_20") (pintype "unspecified+no_connect"))
    )
    (net (code "73") (name "unconnected-(U11-NC-Pad21)") (class "Default")
      (node (ref "U11") (pin "21") (pinfunction "NC_21") (pintype "unspecified+no_connect"))
    )
    (net (code "74") (name "unconnected-(U11-NC-Pad22)") (class "Default")
      (node (ref "U11") (pin "22") (pinfunction "NC_22") (pintype "unspecified+no_connect"))
    )
    (net (code "75") (name "unconnected-(U11-NC-Pad32)") (class "Default")
      (node (ref "U11") (pin "32") (pinfunction "NC_32") (pintype "unspecified+no_connect"))
    )
    (net (code "76") (name "unconnected-(U11-SENSOR_VN-Pad5)") (class "Default")
      (node (ref "U11") (pin "5") (pinfunction "SENSOR_VN_5") (pintype "unspecified+no_connect"))
    )
    (net (code "77") (name "unconnected-(U11-SENSOR_VP-Pad4)") (class "Default")
      (node (ref "U11") (pin "4") (pinfunction "SENSOR_VP_4") (pintype "unspecified+no_connect"))
    )
    (net (code "78") (name "unconnected-(U12-Pad6)") (class "Default")
      (node (ref "U12") (pin "6") (pinfunction "6_6") (pintype "unspecified+no_connect"))
    )
    (net (code "79") (name "unconnected-(U12-Pad7)") (class "Default")
      (node (ref "U12") (pin "7") (pinfunction "7_7") (pintype "unspecified+no_connect"))
    )
  )
)
